# PA_Channel.net
KiCad netlist of a schematic drawn in Altium Designer
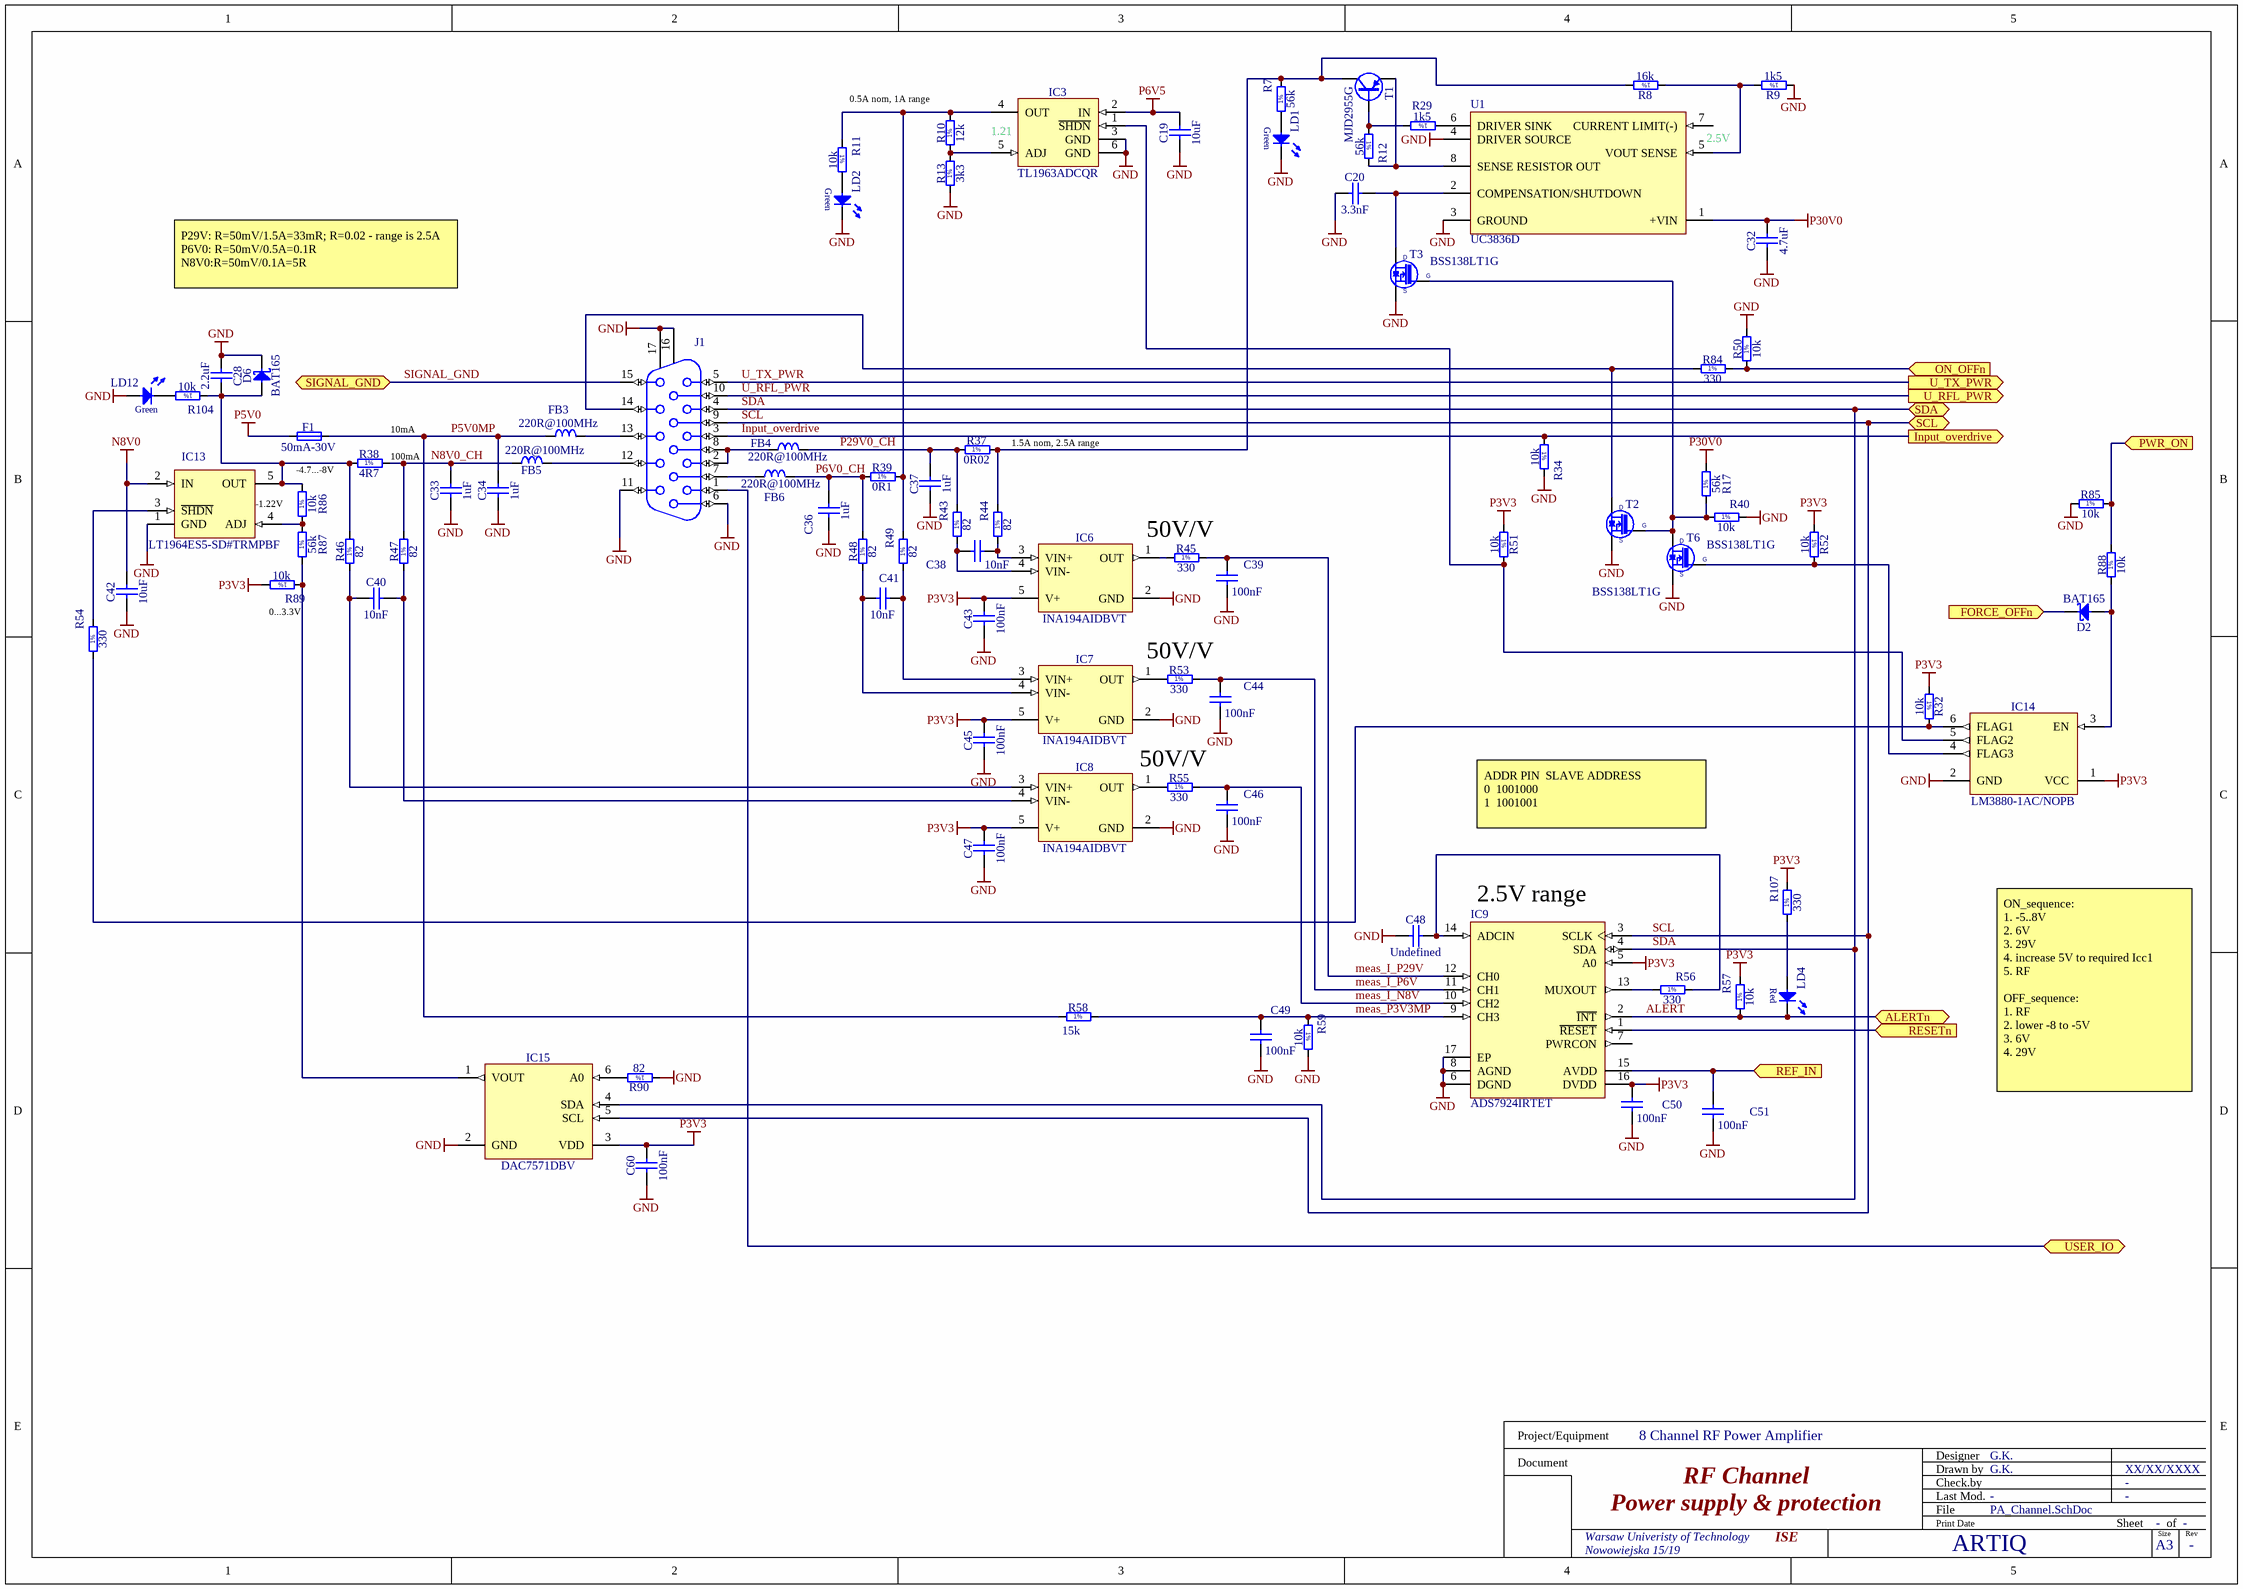
[diagram p0: PA_Channel.SchDoc]

(export (version "E")
  (design (tool "Eeschema 10.0.6"))
  (components
    (comp (ref "C19")
      (value "10uF")
      (footprint "CAPC3216X140N")
      (description "Non-polarised capacitor")
      (fields
        (field (name "PART NUMBER") "CC1206_10UF_16V_10%_X7R")
        (field (name "VOLTAGE") "16V")
        (field (name "AUTHOR") "CERN DEM JLC")
      )
      (libsource (lib "Capacitors") (part "Capacitor - non polarized"))
    )
    (comp (ref "C20")
      (value "3.3nF")
      (footprint "CAPC1005X55N")
      (description "Non-polarised capacitor")
      (fields
        (field (name "PART NUMBER") "CC0402_3.3NF_50V_10%_X7R")
        (field (name "VOLTAGE") "50V")
        (field (name "AUTHOR") "CERN DEM JLC")
      )
      (libsource (lib "Capacitors") (part "Capacitor - non polarized"))
    )
    (comp (ref "C28")
      (value "2.2uF")
      (footprint "CAPC1608X87N")
      (description "Non-polarised capacitor")
      (fields
        (field (name "PART NUMBER") "CC0603_2.2UF_16V_10%_X5R")
        (field (name "VOLTAGE") "16V")
        (field (name "AUTHOR") "CERN DEM JLC")
      )
      (libsource (lib "Capacitors") (part "Capacitor - non polarized"))
    )
    (comp (ref "C32")
      (value "4.7uF")
      (footprint "CAPC3216X180N")
      (description "Non-polarised capacitor")
      (fields
        (field (name "PART NUMBER") "CC1206_4.7UF_50V_+80%-20%_Y5V")
        (field (name "VOLTAGE") "50V")
        (field (name "AUTHOR") "CERN DEM JLC")
      )
      (libsource (lib "Capacitors") (part "Capacitor - non polarized"))
    )
    (comp (ref "C33")
      (value "1uF")
      (footprint "CAPC2012X110N")
      (description "Non-polarised capacitor")
      (fields
        (field (name "PART NUMBER") "CC0805_1UF_50V_10%_X7R")
        (field (name "VOLTAGE") "50V")
        (field (name "AUTHOR") "CERN DEM JLC")
      )
      (libsource (lib "Capacitors") (part "Capacitor - non polarized"))
    )
    (comp (ref "C34")
      (value "1uF")
      (footprint "CAPC2012X110N")
      (description "Non-polarised capacitor")
      (fields
        (field (name "PART NUMBER") "CC0805_1UF_50V_10%_X7R")
        (field (name "VOLTAGE") "50V")
        (field (name "AUTHOR") "CERN DEM JLC")
      )
      (libsource (lib "Capacitors") (part "Capacitor - non polarized"))
    )
    (comp (ref "C36")
      (value "1uF")
      (footprint "CAPC2012X110N")
      (description "Non-polarised capacitor")
      (fields
        (field (name "PART NUMBER") "CC0805_1UF_50V_10%_X7R")
        (field (name "VOLTAGE") "50V")
        (field (name "AUTHOR") "CERN DEM JLC")
      )
      (libsource (lib "Capacitors") (part "Capacitor - non polarized"))
    )
    (comp (ref "C37")
      (value "1uF")
      (footprint "CAPC2012X110N")
      (description "Non-polarised capacitor")
      (fields
        (field (name "PART NUMBER") "CC0805_1UF_50V_10%_X7R")
        (field (name "VOLTAGE") "50V")
        (field (name "AUTHOR") "CERN DEM JLC")
      )
      (libsource (lib "Capacitors") (part "Capacitor - non polarized"))
    )
    (comp (ref "C38")
      (value "10nF")
      (footprint "CAPC1608X87N")
      (description "Non-polarised capacitor")
      (fields
        (field (name "PART NUMBER") "CC0603_10NF_50V_5%_C0G")
        (field (name "VOLTAGE") "50V")
        (field (name "AUTHOR") "CERN DEM JLC")
      )
      (libsource (lib "Capacitors") (part "Capacitor - non polarized"))
    )
    (comp (ref "C39")
      (value "100nF")
      (footprint "CAPC1005X55N")
      (description "Non-polarised capacitor")
      (fields
        (field (name "PART NUMBER") "CC0402_100NF_16V_10%_X7R")
        (field (name "VOLTAGE") "16V")
        (field (name "AUTHOR") "CERN DEM JLC")
      )
      (libsource (lib "Capacitors") (part "Capacitor - non polarized"))
    )
    (comp (ref "C40")
      (value "10nF")
      (footprint "CAPC1608X87N")
      (description "Non-polarised capacitor")
      (fields
        (field (name "PART NUMBER") "CC0603_10NF_50V_5%_C0G")
        (field (name "VOLTAGE") "50V")
        (field (name "AUTHOR") "CERN DEM JLC")
      )
      (libsource (lib "Capacitors") (part "Capacitor - non polarized"))
    )
    (comp (ref "C41")
      (value "10nF")
      (footprint "CAPC1608X87N")
      (description "Non-polarised capacitor")
      (fields
        (field (name "PART NUMBER") "CC0603_10NF_50V_5%_C0G")
        (field (name "VOLTAGE") "50V")
        (field (name "AUTHOR") "CERN DEM JLC")
      )
      (libsource (lib "Capacitors") (part "Capacitor - non polarized"))
    )
    (comp (ref "C42")
      (value "10uF")
      (footprint "CAPC3216X140N")
      (description "Non-polarised capacitor")
      (fields
        (field (name "PART NUMBER") "CC1206_10UF_16V_10%_X7R")
        (field (name "VOLTAGE") "16V")
        (field (name "AUTHOR") "CERN DEM JLC")
      )
      (libsource (lib "Capacitors") (part "Capacitor - non polarized"))
    )
    (comp (ref "C43")
      (value "100nF")
      (footprint "CAPC1005X55N")
      (description "Non-polarised capacitor")
      (fields
        (field (name "PART NUMBER") "CC0402_100NF_16V_10%_X7R")
        (field (name "VOLTAGE") "16V")
        (field (name "AUTHOR") "CERN DEM JLC")
      )
      (libsource (lib "Capacitors") (part "Capacitor - non polarized"))
    )
    (comp (ref "C44")
      (value "100nF")
      (footprint "CAPC1005X55N")
      (description "Non-polarised capacitor")
      (fields
        (field (name "PART NUMBER") "CC0402_100NF_16V_10%_X7R")
        (field (name "VOLTAGE") "16V")
        (field (name "AUTHOR") "CERN DEM JLC")
      )
      (libsource (lib "Capacitors") (part "Capacitor - non polarized"))
    )
    (comp (ref "C45")
      (value "100nF")
      (footprint "CAPC1005X55N")
      (description "Non-polarised capacitor")
      (fields
        (field (name "PART NUMBER") "CC0402_100NF_16V_10%_X7R")
        (field (name "VOLTAGE") "16V")
        (field (name "AUTHOR") "CERN DEM JLC")
      )
      (libsource (lib "Capacitors") (part "Capacitor - non polarized"))
    )
    (comp (ref "C46")
      (value "100nF")
      (footprint "CAPC1005X55N")
      (description "Non-polarised capacitor")
      (fields
        (field (name "PART NUMBER") "CC0402_100NF_16V_10%_X7R")
        (field (name "VOLTAGE") "16V")
        (field (name "AUTHOR") "CERN DEM JLC")
      )
      (libsource (lib "Capacitors") (part "Capacitor - non polarized"))
    )
    (comp (ref "C47")
      (value "100nF")
      (footprint "CAPC1005X55N")
      (description "Non-polarised capacitor")
      (fields
        (field (name "PART NUMBER") "CC0402_100NF_16V_10%_X7R")
        (field (name "VOLTAGE") "16V")
        (field (name "AUTHOR") "CERN DEM JLC")
      )
      (libsource (lib "Capacitors") (part "Capacitor - non polarized"))
    )
    (comp (ref "C48")
      (value "Undefined")
      (footprint "CAPC1005X55N")
      (description "Non-polarised capacitor")
      (fields (field (name "PART NUMBER") "CC0402_NO-VALUE") (field (name "AUTHOR") "CERN DEM JLC"))
      (libsource (lib "Capacitors") (part "Capacitor - non polarized"))
    )
    (comp (ref "C49")
      (value "100nF")
      (footprint "CAPC1005X55N")
      (description "Non-polarised capacitor")
      (fields
        (field (name "PART NUMBER") "CC0402_100NF_16V_10%_X7R")
        (field (name "VOLTAGE") "16V")
        (field (name "AUTHOR") "CERN DEM JLC")
      )
      (libsource (lib "Capacitors") (part "Capacitor - non polarized"))
    )
    (comp (ref "C50")
      (value "100nF")
      (footprint "CAPC1005X55N")
      (description "Non-polarised capacitor")
      (fields
        (field (name "PART NUMBER") "CC0402_100NF_16V_10%_X7R")
        (field (name "VOLTAGE") "16V")
        (field (name "AUTHOR") "CERN DEM JLC")
      )
      (libsource (lib "Capacitors") (part "Capacitor - non polarized"))
    )
    (comp (ref "C51")
      (value "100nF")
      (footprint "CAPC1005X55N")
      (description "Non-polarised capacitor")
      (fields
        (field (name "PART NUMBER") "CC0402_100NF_16V_10%_X7R")
        (field (name "VOLTAGE") "16V")
        (field (name "AUTHOR") "CERN DEM JLC")
      )
      (libsource (lib "Capacitors") (part "Capacitor - non polarized"))
    )
    (comp (ref "C60")
      (value "100nF")
      (footprint "CAPC1005X55N")
      (description "Non-polarised capacitor")
      (fields
        (field (name "PART NUMBER") "CC0402_100NF_16V_10%_X7R")
        (field (name "VOLTAGE") "16V")
        (field (name "AUTHOR") "CERN DEM JLC")
      )
      (libsource (lib "Capacitors") (part "Capacitor - non polarized"))
    )
    (comp (ref "D2")
      (value "BAT165")
      (footprint "SOD2512X110N")
      (description "Schottky Diode")
      (fields
        (field (name "VOLTAGE") "40V")
        (field (name "POWER") "750mA")
        (field (name "AUTHOR") "CERN DEM JLC")
      )
      (libsource (lib "ICs And Semiconductors") (part "Diode Schottky"))
    )
    (comp (ref "D6")
      (value "BAT165")
      (footprint "SOD2512X110N")
      (description "Schottky Diode")
      (fields
        (field (name "VOLTAGE") "40V")
        (field (name "POWER") "750mA")
        (field (name "AUTHOR") "CERN DEM JLC")
      )
      (libsource (lib "ICs And Semiconductors") (part "Diode Schottky"))
    )
    (comp (ref "F1")
      (value "50mA-30V")
      (footprint "FUSRC3226X85N")
      (description "Fuse")
      (fields
        (field (name "PART NUMBER") "FUSR1210_TYCO-MICROSMD005F")
        (field (name "MANUFACTURER") "TYCO ELECTRONICS")
        (field (name "AUTHOR") "CERN DEM JLC")
      )
      (libsource (lib "Eletro-mechanical") (part "Fuse"))
    )
    (comp (ref "FB3")
      (value "220R@100MHz")
      (footprint "INDC2012X105N")
      (description "Inductor")
      (fields
        (field (name "PART NUMBER") "IND0805_MURATA_BLM21PG221SN1D")
        (field (name "POWER") "2A")
        (field (name "AUTHOR") "CERN DEM JLC")
      )
      (libsource (lib "Inductors & Transformers") (part "Inductor"))
    )
    (comp (ref "FB4")
      (value "220R@100MHz")
      (footprint "INDC2012X105N")
      (description "Inductor")
      (fields
        (field (name "PART NUMBER") "IND0805_MURATA_BLM21PG221SN1D")
        (field (name "POWER") "2A")
        (field (name "AUTHOR") "CERN DEM JLC")
      )
      (libsource (lib "Inductors & Transformers") (part "Inductor"))
    )
    (comp (ref "FB5")
      (value "220R@100MHz")
      (footprint "INDC2012X105N")
      (description "Inductor")
      (fields
        (field (name "PART NUMBER") "IND0805_MURATA_BLM21PG221SN1D")
        (field (name "POWER") "2A")
        (field (name "AUTHOR") "CERN DEM JLC")
      )
      (libsource (lib "Inductors & Transformers") (part "Inductor"))
    )
    (comp (ref "FB6")
      (value "220R@100MHz")
      (footprint "INDC2012X105N")
      (description "Inductor")
      (fields
        (field (name "PART NUMBER") "IND0805_MURATA_BLM21PG221SN1D")
        (field (name "POWER") "2A")
        (field (name "AUTHOR") "CERN DEM JLC")
      )
      (libsource (lib "Inductors & Transformers") (part "Inductor"))
    )
    (comp (ref "IC3")
      (value "TL1963ADCQR")
      (footprint "SOT127P700X180-6N")
      (description "1.2V to 20V, 1.5A, Fast Transient Response, Low Noise, LDO Adjustable Regulator")
      (fields (field (name "MANUFACTURER") "TEXAS INSTRUMENTS") (field (name "AUTHOR") "CERN DEM JLC"))
      (libsource (lib "ICs And Semiconductors") (part "TL1963ADCQR"))
    )
    (comp (ref "IC6")
      (value "INA194AIDBVT")
      (footprint "SOT95P280X145-5N")
      (description "Current Shunt Monitor -16V to +80V Common-Mode Range")
      (fields (field (name "MANUFACTURER") "TEXAS INSTRUMENTS") (field (name "AUTHOR") "CERN DEM JLC"))
      (libsource (lib "ICs And Semiconductors") (part "INA194"))
    )
    (comp (ref "IC7")
      (value "INA194AIDBVT")
      (footprint "SOT95P280X145-5N")
      (description "Current Shunt Monitor -16V to +80V Common-Mode Range")
      (fields (field (name "MANUFACTURER") "TEXAS INSTRUMENTS") (field (name "AUTHOR") "CERN DEM JLC"))
      (libsource (lib "ICs And Semiconductors") (part "INA194"))
    )
    (comp (ref "IC8")
      (value "INA194AIDBVT")
      (footprint "SOT95P280X145-5N")
      (description "Current Shunt Monitor -16V to +80V Common-Mode Range")
      (fields (field (name "MANUFACTURER") "TEXAS INSTRUMENTS") (field (name "AUTHOR") "CERN DEM JLC"))
      (libsource (lib "ICs And Semiconductors") (part "INA194"))
    )
    (comp (ref "IC9")
      (value "ADS7924IRTET")
      (footprint "TI-RTE16-1700X1700TP_V")
      (fields (field (name "MANUFACTURER") "Texas Instruments"))
      (libsource (lib "Altium Content Vault") (part "CMP-0003-02162-1"))
    )
    (comp (ref "IC13")
      (value "LT1964ES5-SD#TRMPBF")
      (footprint "SOT95P280X100-5N")
      (description "200mA, Low Noise, Low Dropout Negative Micropower Regulator")
      (fields (field (name "MANUFACTURER") "LINEAR TECHNOLOGY") (field (name "AUTHOR") "CERN DEM JLC"))
      (libsource (lib "ICs And Semiconductors") (part "LT1964-SD"))
    )
    (comp (ref "IC14")
      (value "LM3880-1AC/NOPB")
      (footprint "SOT95P280X145-6N")
      (description "Simple Power Sequencer")
      (fields (field (name "MANUFACTURER") "TEXAS INSTRUMENTS") (field (name "AUTHOR") "CERN DEM MR"))
      (libsource (lib "ICs And Semiconductors") (part "LM3880"))
    )
    (comp (ref "IC15")
      (value "DAC7571DBV")
      (footprint "SOT95P280X145-6N")
      (description "+2.7 V to +5.5 V, I2C Interface (Receive Only), Voltage Output, 12-Bit Digital-To-Analog Converter")
      (fields (field (name "MANUFACTURER") "TEXAS INSTRUMENTS") (field (name "AUTHOR") "CERN DEM MR"))
      (libsource (lib "ICs And Semiconductors") (part "DAC7571"))
    )
    (comp (ref "J1")
      (value "HD-Sub")
      (footprint "TYCO_1932144-1")
      (description "Connector High Density D-sub 15 Female")
      (fields
        (field (name "PART NUMBER") "TYCO_1932144-1")
        (field (name "MANUFACTURER") "TYCO ELECTRONICS")
        (field (name "AUTHOR") "GK")
      )
      (libsource (lib "LIBRARY_SCH") (part "CON_DB15_V_F_1932144-1"))
    )
    (comp (ref "LD1")
      (value "Green")
      (footprint "LED_KINGBRIGHT_KPH-1608CGCK")
      (description "LED Green 1C 2A")
      (fields
        (field (name "PART NUMBER") "LED_KINGBRIGHT_KPH-1608CGCK")
        (field (name "MANUFACTURER") "KINGBRIGHT")
        (field (name "AUTHOR") "CERN DEM JLC")
      )
      (libsource (lib "ICs And Semiconductors") (part "LED Green 1C 2A"))
    )
    (comp (ref "LD2")
      (value "Green")
      (footprint "LED_KINGBRIGHT_KPH-1608CGCK")
      (description "LED Green 1C 2A")
      (fields
        (field (name "PART NUMBER") "LED_KINGBRIGHT_KPH-1608CGCK")
        (field (name "MANUFACTURER") "KINGBRIGHT")
        (field (name "AUTHOR") "CERN DEM JLC")
      )
      (libsource (lib "ICs And Semiconductors") (part "LED Green 1C 2A"))
    )
    (comp (ref "LD4")
      (value "Hyper Red")
      (footprint "LED_KINGBRIGHT_KPH-1608SURCK")
      (description "LED Red 1C 2A")
      (fields
        (field (name "PART NUMBER") "LED_KINGBRIGHT_KPH-1608SURCK")
        (field (name "MANUFACTURER") "KINGBRIGHT")
        (field (name "AUTHOR") "CERN DEM JLC")
      )
      (libsource (lib "ICs And Semiconductors") (part "LED Red 1C 2A"))
    )
    (comp (ref "LD12")
      (value "Green")
      (footprint "LED_KINGBRIGHT_KPH-1608CGCK")
      (description "LED Green 1C 2A")
      (fields
        (field (name "PART NUMBER") "LED_KINGBRIGHT_KPH-1608CGCK")
        (field (name "MANUFACTURER") "KINGBRIGHT")
        (field (name "AUTHOR") "CERN DEM JLC")
      )
      (libsource (lib "ICs And Semiconductors") (part "LED Green 1C 2A"))
    )
    (comp (ref "R7")
      (value "56k")
      (footprint "RESC1608X55N")
      (description "Resistor - 1%")
      (fields
        (field (name "PART NUMBER") "R0603_56K_1%_0.1W_100PPM")
        (field (name "POWER") "0.1W")
        (field (name "AUTHOR") "CERN DEM JLC")
      )
      (libsource (lib "Resistors") (part "Resistor - 1%"))
    )
    (comp (ref "R8")
      (value "16k")
      (footprint "RESC1608X55N")
      (description "Resistor - 1%")
      (fields
        (field (name "PART NUMBER") "R0603_16K_1%_0.1W_100PPM")
        (field (name "POWER") "0.1W")
        (field (name "AUTHOR") "CERN DEM JLC")
      )
      (libsource (lib "Resistors") (part "Resistor - 1%"))
    )
    (comp (ref "R9")
      (value "1k5")
      (footprint "RESC1608X55N")
      (description "Resistor - 1%")
      (fields
        (field (name "PART NUMBER") "R0603_1K5_1%_0.1W_100PPM")
        (field (name "POWER") "0.1W")
        (field (name "AUTHOR") "CERN DEM JLC")
      )
      (libsource (lib "Resistors") (part "Resistor - 1%"))
    )
    (comp (ref "R10")
      (value "12k")
      (footprint "RESC1005X40N")
      (description "Resistor - 1%")
      (fields
        (field (name "PART NUMBER") "R0402_12K_1%_0.0625W_100PPM")
        (field (name "POWER") "0.0625W")
        (field (name "AUTHOR") "CERN DEM JLC")
      )
      (libsource (lib "Resistors") (part "Resistor - 1%"))
    )
    (comp (ref "R11")
      (value "10k")
      (footprint "RESC1005X40N")
      (description "Resistor - 1%")
      (fields
        (field (name "PART NUMBER") "R0402_10K_1%_0.0625W_100PPM")
        (field (name "POWER") "0.0625W")
        (field (name "AUTHOR") "CERN DEM JLC")
      )
      (libsource (lib "Resistors") (part "Resistor - 1%"))
    )
    (comp (ref "R12")
      (value "56k")
      (footprint "RESC1608X55N")
      (description "Resistor - 1%")
      (fields
        (field (name "PART NUMBER") "R0603_56K_1%_0.1W_100PPM")
        (field (name "POWER") "0.1W")
        (field (name "AUTHOR") "CERN DEM JLC")
      )
      (libsource (lib "Resistors") (part "Resistor - 1%"))
    )
    (comp (ref "R13")
      (value "3k3")
      (footprint "RESC1005X40N")
      (description "Resistor - 1%")
      (fields
        (field (name "PART NUMBER") "R0402_3K3_1%_0.0625W_100PPM")
        (field (name "POWER") "0.0625W")
        (field (name "AUTHOR") "CERN DEM JLC")
      )
      (libsource (lib "Resistors") (part "Resistor - 1%"))
    )
    (comp (ref "R17")
      (value "56k")
      (footprint "RESC1608X55N")
      (description "Resistor - 1%")
      (fields
        (field (name "PART NUMBER") "R0603_56K_1%_0.1W_100PPM")
        (field (name "POWER") "0.1W")
        (field (name "AUTHOR") "CERN DEM JLC")
      )
      (libsource (lib "Resistors") (part "Resistor - 1%"))
    )
    (comp (ref "R29")
      (value "1k5")
      (footprint "RESC1608X55N")
      (description "Resistor - 1%")
      (fields
        (field (name "PART NUMBER") "R0603_1K5_1%_0.1W_100PPM")
        (field (name "POWER") "0.1W")
        (field (name "AUTHOR") "CERN DEM JLC")
      )
      (libsource (lib "Resistors") (part "Resistor - 1%"))
    )
    (comp (ref "R32")
      (value "10k")
      (footprint "RESC1005X40N")
      (description "Resistor - 1%")
      (fields
        (field (name "PART NUMBER") "R0402_10K_1%_0.0625W_100PPM")
        (field (name "POWER") "0.0625W")
        (field (name "AUTHOR") "CERN DEM JLC")
      )
      (libsource (lib "Resistors") (part "Resistor - 1%"))
    )
    (comp (ref "R34")
      (value "10k")
      (footprint "RESC1005X40N")
      (description "Resistor - 1%")
      (fields
        (field (name "PART NUMBER") "R0402_10K_1%_0.0625W_100PPM")
        (field (name "POWER") "0.0625W")
        (field (name "AUTHOR") "CERN DEM JLC")
      )
      (libsource (lib "Resistors") (part "Resistor - 1%"))
    )
    (comp (ref "R37")
      (value "0R02")
      (footprint "RESC3216X80N")
      (description "Resistor - 1%")
      (fields
        (field (name "PART NUMBER") "R1206_0R02_1%_1W_150PPM")
        (field (name "POWER") "1W")
        (field (name "AUTHOR") "CERN DEM JLC")
      )
      (libsource (lib "Resistors") (part "Resistor - 1%"))
    )
    (comp (ref "R38")
      (value "4R7")
      (footprint "RESC3216X65N")
      (description "Resistor - 1%")
      (fields
        (field (name "PART NUMBER") "R1206_4R7_1%_0.25W_200PPM")
        (field (name "POWER") "0.25W")
        (field (name "AUTHOR") "CERN DEM JLC")
      )
      (libsource (lib "Resistors") (part "Resistor - 1%"))
    )
    (comp (ref "R39")
      (value "0R1")
      (footprint "RESC3216X65N")
      (description "Resistor - 1%")
      (fields
        (field (name "PART NUMBER") "R1206_0R1_1%_0.25W_100PPM_YAGEO_PT")
        (field (name "POWER") "0.25W")
        (field (name "AUTHOR") "CERN DEM JMW")
      )
      (libsource (lib "Resistors") (part "Resistor - 1%"))
    )
    (comp (ref "R40")
      (value "10k")
      (footprint "RESC1005X40N")
      (description "Resistor - 1%")
      (fields
        (field (name "PART NUMBER") "R0402_10K_1%_0.0625W_100PPM")
        (field (name "POWER") "0.0625W")
        (field (name "AUTHOR") "CERN DEM JLC")
      )
      (libsource (lib "Resistors") (part "Resistor - 1%"))
    )
    (comp (ref "R43")
      (value "82")
      (footprint "RESC1005X40N")
      (description "Resistor - 1%")
      (fields
        (field (name "PART NUMBER") "R0402_82R_1%_0.0625W_100PPM")
        (field (name "POWER") "0.0625W")
        (field (name "AUTHOR") "CERN DEM JLC")
      )
      (libsource (lib "Resistors") (part "Resistor - 1%"))
    )
    (comp (ref "R44")
      (value "82")
      (footprint "RESC1005X40N")
      (description "Resistor - 1%")
      (fields
        (field (name "PART NUMBER") "R0402_82R_1%_0.0625W_100PPM")
        (field (name "POWER") "0.0625W")
        (field (name "AUTHOR") "CERN DEM JLC")
      )
      (libsource (lib "Resistors") (part "Resistor - 1%"))
    )
    (comp (ref "R45")
      (value "330")
      (footprint "RESC1608X55N")
      (description "Resistor - 1%")
      (fields
        (field (name "PART NUMBER") "R0603_330R_1%_0.1W_100PPM")
        (field (name "POWER") "0.1W")
        (field (name "AUTHOR") "CERN DEM JLC")
      )
      (libsource (lib "Resistors") (part "Resistor - 1%"))
    )
    (comp (ref "R46")
      (value "82")
      (footprint "RESC1005X40N")
      (description "Resistor - 1%")
      (fields
        (field (name "PART NUMBER") "R0402_82R_1%_0.0625W_100PPM")
        (field (name "POWER") "0.0625W")
        (field (name "AUTHOR") "CERN DEM JLC")
      )
      (libsource (lib "Resistors") (part "Resistor - 1%"))
    )
    (comp (ref "R47")
      (value "82")
      (footprint "RESC1005X40N")
      (description "Resistor - 1%")
      (fields
        (field (name "PART NUMBER") "R0402_82R_1%_0.0625W_100PPM")
        (field (name "POWER") "0.0625W")
        (field (name "AUTHOR") "CERN DEM JLC")
      )
      (libsource (lib "Resistors") (part "Resistor - 1%"))
    )
    (comp (ref "R48")
      (value "82")
      (footprint "RESC1005X40N")
      (description "Resistor - 1%")
      (fields
        (field (name "PART NUMBER") "R0402_82R_1%_0.0625W_100PPM")
        (field (name "POWER") "0.0625W")
        (field (name "AUTHOR") "CERN DEM JLC")
      )
      (libsource (lib "Resistors") (part "Resistor - 1%"))
    )
    (comp (ref "R49")
      (value "82")
      (footprint "RESC1005X40N")
      (description "Resistor - 1%")
      (fields
        (field (name "PART NUMBER") "R0402_82R_1%_0.0625W_100PPM")
        (field (name "POWER") "0.0625W")
        (field (name "AUTHOR") "CERN DEM JLC")
      )
      (libsource (lib "Resistors") (part "Resistor - 1%"))
    )
    (comp (ref "R50")
      (value "10k")
      (footprint "RESC1005X40N")
      (description "Resistor - 1%")
      (fields
        (field (name "PART NUMBER") "R0402_10K_1%_0.0625W_100PPM")
        (field (name "POWER") "0.0625W")
        (field (name "AUTHOR") "CERN DEM JLC")
      )
      (libsource (lib "Resistors") (part "Resistor - 1%"))
    )
    (comp (ref "R51")
      (value "10k")
      (footprint "RESC1005X40N")
      (description "Resistor - 1%")
      (fields
        (field (name "PART NUMBER") "R0402_10K_1%_0.0625W_100PPM")
        (field (name "POWER") "0.0625W")
        (field (name "AUTHOR") "CERN DEM JLC")
      )
      (libsource (lib "Resistors") (part "Resistor - 1%"))
    )
    (comp (ref "R52")
      (value "10k")
      (footprint "RESC1005X40N")
      (description "Resistor - 1%")
      (fields
        (field (name "PART NUMBER") "R0402_10K_1%_0.0625W_100PPM")
        (field (name "POWER") "0.0625W")
        (field (name "AUTHOR") "CERN DEM JLC")
      )
      (libsource (lib "Resistors") (part "Resistor - 1%"))
    )
    (comp (ref "R53")
      (value "330")
      (footprint "RESC1608X55N")
      (description "Resistor - 1%")
      (fields
        (field (name "PART NUMBER") "R0603_330R_1%_0.1W_100PPM")
        (field (name "POWER") "0.1W")
        (field (name "AUTHOR") "CERN DEM JLC")
      )
      (libsource (lib "Resistors") (part "Resistor - 1%"))
    )
    (comp (ref "R54")
      (value "330")
      (footprint "RESC1608X55N")
      (description "Resistor - 1%")
      (fields
        (field (name "PART NUMBER") "R0603_330R_1%_0.1W_100PPM")
        (field (name "POWER") "0.1W")
        (field (name "AUTHOR") "CERN DEM JLC")
      )
      (libsource (lib "Resistors") (part "Resistor - 1%"))
    )
    (comp (ref "R55")
      (value "330")
      (footprint "RESC1608X55N")
      (description "Resistor - 1%")
      (fields
        (field (name "PART NUMBER") "R0603_330R_1%_0.1W_100PPM")
        (field (name "POWER") "0.1W")
        (field (name "AUTHOR") "CERN DEM JLC")
      )
      (libsource (lib "Resistors") (part "Resistor - 1%"))
    )
    (comp (ref "R56")
      (value "330")
      (footprint "RESC1608X55N")
      (description "Resistor - 1%")
      (fields
        (field (name "PART NUMBER") "R0603_330R_1%_0.1W_100PPM")
        (field (name "POWER") "0.1W")
        (field (name "AUTHOR") "CERN DEM JLC")
      )
      (libsource (lib "Resistors") (part "Resistor - 1%"))
    )
    (comp (ref "R57")
      (value "10k")
      (footprint "RESC1005X40N")
      (description "Resistor - 1%")
      (fields
        (field (name "PART NUMBER") "R0402_10K_1%_0.0625W_100PPM")
        (field (name "POWER") "0.0625W")
        (field (name "AUTHOR") "CERN DEM JLC")
      )
      (libsource (lib "Resistors") (part "Resistor - 1%"))
    )
    (comp (ref "R58")
      (value "15k")
      (footprint "RESC1005X40N")
      (description "Resistor - 1%")
      (fields
        (field (name "PART NUMBER") "R0402_15K_1%_0.0625W_100PPM")
        (field (name "POWER") "0.0625W")
        (field (name "AUTHOR") "CERN DEM JMW")
      )
      (libsource (lib "Resistors") (part "Resistor - 1%"))
    )
    (comp (ref "R59")
      (value "10k")
      (footprint "RESC1005X40N")
      (description "Resistor - 1%")
      (fields
        (field (name "PART NUMBER") "R0402_10K_1%_0.0625W_100PPM")
        (field (name "POWER") "0.0625W")
        (field (name "AUTHOR") "CERN DEM JLC")
      )
      (libsource (lib "Resistors") (part "Resistor - 1%"))
    )
    (comp (ref "R84")
      (value "330")
      (footprint "RESC1608X55N")
      (description "Resistor - 1%")
      (fields
        (field (name "PART NUMBER") "R0603_330R_1%_0.1W_100PPM")
        (field (name "POWER") "0.1W")
        (field (name "AUTHOR") "CERN DEM JLC")
      )
      (libsource (lib "Resistors") (part "Resistor - 1%"))
    )
    (comp (ref "R85")
      (value "10k")
      (footprint "RESC1005X40N")
      (description "Resistor - 1%")
      (fields
        (field (name "PART NUMBER") "R0402_10K_1%_0.0625W_100PPM")
        (field (name "POWER") "0.0625W")
        (field (name "AUTHOR") "CERN DEM JLC")
      )
      (libsource (lib "Resistors") (part "Resistor - 1%"))
    )
    (comp (ref "R86")
      (value "10k")
      (footprint "RESC1005X40N")
      (description "Resistor - 1%")
      (fields
        (field (name "PART NUMBER") "R0402_10K_1%_0.0625W_100PPM")
        (field (name "POWER") "0.0625W")
        (field (name "AUTHOR") "CERN DEM JLC")
      )
      (libsource (lib "Resistors") (part "Resistor - 1%"))
    )
    (comp (ref "R87")
      (value "56k")
      (footprint "RESC1608X55N")
      (description "Resistor - 1%")
      (fields
        (field (name "PART NUMBER") "R0603_56K_1%_0.1W_100PPM")
        (field (name "POWER") "0.1W")
        (field (name "AUTHOR") "CERN DEM JLC")
      )
      (libsource (lib "Resistors") (part "Resistor - 1%"))
    )
    (comp (ref "R88")
      (value "10k")
      (footprint "RESC1005X40N")
      (description "Resistor - 1%")
      (fields
        (field (name "PART NUMBER") "R0402_10K_1%_0.0625W_100PPM")
        (field (name "POWER") "0.0625W")
        (field (name "AUTHOR") "CERN DEM JLC")
      )
      (libsource (lib "Resistors") (part "Resistor - 1%"))
    )
    (comp (ref "R89")
      (value "10k")
      (footprint "RESC1005X40N")
      (description "Resistor - 1%")
      (fields
        (field (name "PART NUMBER") "R0402_10K_1%_0.0625W_100PPM")
        (field (name "POWER") "0.0625W")
        (field (name "AUTHOR") "CERN DEM JLC")
      )
      (libsource (lib "Resistors") (part "Resistor - 1%"))
    )
    (comp (ref "R90")
      (value "82")
      (footprint "RESC1005X40N")
      (description "Resistor - 1%")
      (fields
        (field (name "PART NUMBER") "R0402_82R_1%_0.0625W_100PPM")
        (field (name "POWER") "0.0625W")
        (field (name "AUTHOR") "CERN DEM JLC")
      )
      (libsource (lib "Resistors") (part "Resistor - 1%"))
    )
    (comp (ref "R104")
      (value "10k")
      (footprint "RESC1005X40N")
      (description "Resistor - 1%")
      (fields
        (field (name "PART NUMBER") "R0402_10K_1%_0.0625W_100PPM")
        (field (name "POWER") "0.0625W")
        (field (name "AUTHOR") "CERN DEM JLC")
      )
      (libsource (lib "Resistors") (part "Resistor - 1%"))
    )
    (comp (ref "R107")
      (value "330")
      (footprint "RESC1608X55N")
      (description "Resistor - 1%")
      (fields
        (field (name "PART NUMBER") "R0603_330R_1%_0.1W_100PPM")
        (field (name "POWER") "0.1W")
        (field (name "AUTHOR") "CERN DEM JLC")
      )
      (libsource (lib "Resistors") (part "Resistor - 1%"))
    )
    (comp (ref "T1")
      (value "MJD2955G")
      (footprint "TO228P991X239-3N-R552X520")
      (description "PNP Transistor")
      (fields (field (name "MANUFACTURER") "ON SEMICONDUCTOR") (field (name "AUTHOR") "CERN DEM JLC"))
      (libsource (lib "ICs And Semiconductors") (part "PNP B1 E2 C3"))
    )
    (comp (ref "T2")
      (value "BSS138LT1G")
      (footprint "SOT95P240X110-3N")
      (description "N-CHANNEL MOSFET WITH DIODE")
      (fields (field (name "MANUFACTURER") "ON SEMICONDUCTOR") (field (name "AUTHOR") "CERN DEM JLC"))
      (libsource (lib "ICs And Semiconductors") (part "N-MOSFET-D 1G 2S 3D"))
    )
    (comp (ref "T3")
      (value "BSS138LT1G")
      (footprint "SOT95P240X110-3N")
      (description "N-CHANNEL MOSFET WITH DIODE")
      (fields (field (name "MANUFACTURER") "ON SEMICONDUCTOR") (field (name "AUTHOR") "CERN DEM JLC"))
      (libsource (lib "ICs And Semiconductors") (part "N-MOSFET-D 1G 2S 3D"))
    )
    (comp (ref "T6")
      (value "BSS138LT1G")
      (footprint "SOT95P240X110-3N")
      (description "N-CHANNEL MOSFET WITH DIODE")
      (fields (field (name "MANUFACTURER") "ON SEMICONDUCTOR") (field (name "AUTHOR") "CERN DEM JLC"))
      (libsource (lib "ICs And Semiconductors") (part "N-MOSFET-D 1G 2S 3D"))
    )
    (comp (ref "U1")
      (value "UC3836D")
      (footprint "D0008A_M")
      (fields (field (name "MANUFACTURER") "Texas Instruments"))
      (libsource (lib "Altium Content Vault") (part "CMP-0322-00047-2"))
    )
  )
  (nets
    (net (code "1") (name "/ALERT") (class "Default")
      (node (ref "IC9") (pin "2") (pinfunction "~{INT}_2") (pintype "output"))
      (node (ref "LD4") (pin "1") (pinfunction "C_1") (pintype "passive"))
      (node (ref "R57") (pin "1") (pinfunction "1_1") (pintype "passive"))
    )
    (net (code "2") (name "/FORCE_OFFn") (class "Default")
      (node (ref "D2") (pin "1") (pinfunction "C_1") (pintype "passive"))
    )
    (net (code "3") (name "/Input_overdrive") (class "Default")
      (node (ref "J1") (pin "3") (pinfunction "3_3") (pintype "bidirectional"))
      (node (ref "R34") (pin "1") (pinfunction "1_1") (pintype "passive"))
    )
    (net (code "4") (name "/N8V0_CH") (class "Default")
      (node (ref "C33") (pin "2") (pinfunction "2_2") (pintype "passive"))
      (node (ref "FB5") (pin "1") (pinfunction "1_1") (pintype "passive"))
      (node (ref "R38") (pin "2") (pinfunction "2_2") (pintype "passive"))
      (node (ref "R47") (pin "2") (pinfunction "2_2") (pintype "passive"))
    )
    (net (code "5") (name "/ON_OFFn") (class "Default")
      (node (ref "R50") (pin "1") (pinfunction "1_1") (pintype "passive"))
      (node (ref "R84") (pin "2") (pinfunction "2_2") (pintype "passive"))
    )
    (net (code "6") (name "/P5V0MP") (class "Default")
      (node (ref "C34") (pin "2") (pinfunction "2_2") (pintype "passive"))
      (node (ref "F1") (pin "2") (pinfunction "2_2") (pintype "passive"))
      (node (ref "FB3") (pin "1") (pinfunction "1_1") (pintype "passive"))
      (node (ref "R58") (pin "1") (pinfunction "1_1") (pintype "passive"))
    )
    (net (code "7") (name "/P6V0_CH") (class "Default")
      (node (ref "C36") (pin "2") (pinfunction "2_2") (pintype "passive"))
      (node (ref "FB6") (pin "2") (pinfunction "2_2") (pintype "passive"))
      (node (ref "R39") (pin "1") (pinfunction "1_1") (pintype "passive"))
      (node (ref "R48") (pin "2") (pinfunction "2_2") (pintype "passive"))
    )
    (net (code "8") (name "/P29V0_CH") (class "Default")
      (node (ref "C37") (pin "2") (pinfunction "2_2") (pintype "passive"))
      (node (ref "FB4") (pin "2") (pinfunction "2_2") (pintype "passive"))
      (node (ref "R37") (pin "1") (pinfunction "1_1") (pintype "passive"))
      (node (ref "R43") (pin "2") (pinfunction "2_2") (pintype "passive"))
    )
    (net (code "9") (name "/PWR_ON") (class "Default")
      (node (ref "R85") (pin "2") (pinfunction "2_2") (pintype "passive"))
      (node (ref "R88") (pin "2") (pinfunction "2_2") (pintype "passive"))
    )
    (net (code "10") (name "/REF_IN") (class "Default")
      (node (ref "C51") (pin "1") (pinfunction "1_1") (pintype "passive"))
      (node (ref "IC9") (pin "15") (pinfunction "AVDD_15") (pintype "power_in"))
    )
    (net (code "11") (name "/RESETn") (class "Default")
      (node (ref "IC9") (pin "1") (pinfunction "~{RESET}_1") (pintype "input"))
    )
    (net (code "12") (name "/SCL") (class "Default")
      (node (ref "IC15") (pin "5") (pinfunction "SCL_5") (pintype "input"))
      (node (ref "IC9") (pin "3") (pinfunction "SCLK_3") (pintype "input"))
      (node (ref "J1") (pin "9") (pinfunction "9_9") (pintype "bidirectional"))
    )
    (net (code "13") (name "/SDA") (class "Default")
      (node (ref "IC15") (pin "4") (pinfunction "SDA_4") (pintype "input"))
      (node (ref "IC9") (pin "4") (pinfunction "SDA_4") (pintype "bidirectional"))
      (node (ref "J1") (pin "4") (pinfunction "4_4") (pintype "bidirectional"))
    )
    (net (code "14") (name "/SIGNAL_GND") (class "Default")
      (node (ref "J1") (pin "15") (pinfunction "15_15") (pintype "bidirectional"))
    )
    (net (code "15") (name "/USER_IO") (class "Default")
      (node (ref "J1") (pin "1") (pinfunction "1_1") (pintype "bidirectional"))
    )
    (net (code "16") (name "/U_RFL_PWR") (class "Default")
      (node (ref "J1") (pin "10") (pinfunction "10_10") (pintype "bidirectional"))
    )
    (net (code "17") (name "/U_TX_PWR") (class "Default")
      (node (ref "J1") (pin "5") (pinfunction "5_5") (pintype "bidirectional"))
    )
    (net (code "18") (name "/meas_I_N8V") (class "Default")
      (node (ref "C46") (pin "1") (pinfunction "1_1") (pintype "passive"))
      (node (ref "IC9") (pin "10") (pinfunction "CH2_10") (pintype "input"))
      (node (ref "R55") (pin "2") (pinfunction "2_2") (pintype "passive"))
    )
    (net (code "19") (name "/meas_I_P6V") (class "Default")
      (node (ref "C44") (pin "1") (pinfunction "1_1") (pintype "passive"))
      (node (ref "IC9") (pin "11") (pinfunction "CH1_11") (pintype "input"))
      (node (ref "R53") (pin "2") (pinfunction "2_2") (pintype "passive"))
    )
    (net (code "20") (name "/meas_I_P29V") (class "Default")
      (node (ref "C39") (pin "1") (pinfunction "1_1") (pintype "passive"))
      (node (ref "IC9") (pin "12") (pinfunction "CH0_12") (pintype "input"))
      (node (ref "R45") (pin "2") (pinfunction "2_2") (pintype "passive"))
    )
    (net (code "21") (name "/meas_P3V3MP") (class "Default")
      (node (ref "C49") (pin "1") (pinfunction "1_1") (pintype "passive"))
      (node (ref "IC9") (pin "9") (pinfunction "CH3_9") (pintype "input"))
      (node (ref "R58") (pin "2") (pinfunction "2_2") (pintype "passive"))
      (node (ref "R59") (pin "1") (pinfunction "1_1") (pintype "passive"))
    )
    (net (code "22") (name "GND") (class "Default")
      (node (ref "C19") (pin "1") (pinfunction "1_1") (pintype "passive"))
      (node (ref "C20") (pin "1") (pinfunction "1_1") (pintype "passive"))
      (node (ref "C28") (pin "1") (pinfunction "1_1") (pintype "passive"))
      (node (ref "C32") (pin "1") (pinfunction "1_1") (pintype "passive"))
      (node (ref "C33") (pin "1") (pinfunction "1_1") (pintype "passive"))
      (node (ref "C34") (pin "1") (pinfunction "1_1") (pintype "passive"))
      (node (ref "C36") (pin "1") (pinfunction "1_1") (pintype "passive"))
      (node (ref "C37") (pin "1") (pinfunction "1_1") (pintype "passive"))
      (node (ref "C39") (pin "2") (pinfunction "2_2") (pintype "passive"))
      (node (ref "C42") (pin "1") (pinfunction "1_1") (pintype "passive"))
      (node (ref "C43") (pin "1") (pinfunction "1_1") (pintype "passive"))
      (node (ref "C44") (pin "2") (pinfunction "2_2") (pintype "passive"))
      (node (ref "C45") (pin "1") (pinfunction "1_1") (pintype "passive"))
      (node (ref "C46") (pin "2") (pinfunction "2_2") (pintype "passive"))
      (node (ref "C47") (pin "1") (pinfunction "1_1") (pintype "passive"))
      (node (ref "C48") (pin "1") (pinfunction "1_1") (pintype "passive"))
      (node (ref "C49") (pin "2") (pinfunction "2_2") (pintype "passive"))
      (node (ref "C50") (pin "2") (pinfunction "2_2") (pintype "passive"))
      (node (ref "C51") (pin "2") (pinfunction "2_2") (pintype "passive"))
      (node (ref "C60") (pin "1") (pinfunction "1_1") (pintype "passive"))
      (node (ref "D6") (pin "1") (pinfunction "C_1") (pintype "passive"))
      (node (ref "IC13") (pin "1") (pinfunction "GND_1") (pintype "power_in"))
      (node (ref "IC14") (pin "2") (pinfunction "GND_2") (pintype "power_in"))
      (node (ref "IC15") (pin "2") (pinfunction "GND_2") (pintype "power_in"))
      (node (ref "IC3") (pin "3") (pinfunction "GND_3") (pintype "power_in"))
      (node (ref "IC3") (pin "6") (pinfunction "GND_6") (pintype "power_in"))
      (node (ref "IC6") (pin "2") (pinfunction "GND_2") (pintype "power_in"))
      (node (ref "IC7") (pin "2") (pinfunction "GND_2") (pintype "power_in"))
      (node (ref "IC8") (pin "2") (pinfunction "GND_2") (pintype "power_in"))
      (node (ref "IC9") (pin "17") (pinfunction "EP_17") (pintype "power_in"))
      (node (ref "IC9") (pin "6") (pinfunction "DGND_6") (pintype "power_in"))
      (node (ref "IC9") (pin "8") (pinfunction "AGND_8") (pintype "power_in"))
      (node (ref "J1") (pin "11") (pinfunction "11_11") (pintype "bidirectional"))
      (node (ref "J1") (pin "16") (pinfunction "16_16") (pintype "passive"))
      (node (ref "J1") (pin "17") (pinfunction "17_17") (pintype "passive"))
      (node (ref "J1") (pin "6") (pinfunction "6_6") (pintype "bidirectional"))
      (node (ref "LD1") (pin "1") (pinfunction "C_1") (pintype "passive"))
      (node (ref "LD12") (pin "2") (pinfunction "A_2") (pintype "passive"))
      (node (ref "LD2") (pin "1") (pinfunction "C_1") (pintype "passive"))
      (node (ref "R13") (pin "1") (pinfunction "1_1") (pintype "passive"))
      (node (ref "R34") (pin "2") (pinfunction "2_2") (pintype "passive"))
      (node (ref "R40") (pin "2") (pinfunction "2_2") (pintype "passive"))
      (node (ref "R50") (pin "2") (pinfunction "2_2") (pintype "passive"))
      (node (ref "R59") (pin "2") (pinfunction "2_2") (pintype "passive"))
      (node (ref "R85") (pin "1") (pinfunction "1_1") (pintype "passive"))
      (node (ref "R9") (pin "1") (pinfunction "1_1") (pintype "passive"))
      (node (ref "R90") (pin "1") (pinfunction "1_1") (pintype "passive"))
      (node (ref "T2") (pin "2") (pinfunction "S_2") (pintype "passive"))
      (node (ref "T3") (pin "2") (pinfunction "S_2") (pintype "passive"))
      (node (ref "T6") (pin "2") (pinfunction "S_2") (pintype "passive"))
      (node (ref "U1") (pin "3") (pinfunction "GROUND_3") (pintype "power_in"))
      (node (ref "U1") (pin "4") (pinfunction "DRIVER_SOURCE_4") (pintype "passive"))
    )
    (net (code "23") (name "N8V0") (class "Default")
      (node (ref "C42") (pin "2") (pinfunction "2_2") (pintype "passive"))
      (node (ref "IC13") (pin "2") (pinfunction "IN_2") (pintype "input"))
    )
    (net (code "24") (name "Net-(D2-A)") (class "Default")
      (node (ref "D2") (pin "2") (pinfunction "A_2") (pintype "passive"))
      (node (ref "IC14") (pin "3") (pinfunction "EN_3") (pintype "input"))
      (node (ref "R88") (pin "1") (pinfunction "1_1") (pintype "passive"))
    )
    (net (code "25") (name "Net-(D6-A)") (class "Default")
      (node (ref "C28") (pin "2") (pinfunction "2_2") (pintype "passive"))
      (node (ref "D6") (pin "2") (pinfunction "A_2") (pintype "passive"))
      (node (ref "IC13") (pin "5") (pinfunction "OUT_5") (pintype "power_in"))
      (node (ref "R104") (pin "1") (pinfunction "1_1") (pintype "passive"))
      (node (ref "R38") (pin "1") (pinfunction "1_1") (pintype "passive"))
      (node (ref "R46") (pin "2") (pinfunction "2_2") (pintype "passive"))
      (node (ref "R86") (pin "2") (pinfunction "2_2") (pintype "passive"))
    )
    (net (code "26") (name "Net-(FB3-Pad2)") (class "Default")
      (node (ref "FB3") (pin "2") (pinfunction "2_2") (pintype "passive"))
      (node (ref "J1") (pin "13") (pinfunction "13_13") (pintype "bidirectional"))
    )
    (net (code "27") (name "Net-(FB4-Pad1)") (class "Default")
      (node (ref "FB4") (pin "1") (pinfunction "1_1") (pintype "passive"))
      (node (ref "J1") (pin "2") (pinfunction "2_2") (pintype "bidirectional"))
      (node (ref "J1") (pin "8") (pinfunction "8_8") (pintype "bidirectional"))
    )
    (net (code "28") (name "Net-(FB5-Pad2)") (class "Default")
      (node (ref "FB5") (pin "2") (pinfunction "2_2") (pintype "passive"))
      (node (ref "J1") (pin "12") (pinfunction "12_12") (pintype "bidirectional"))
    )
    (net (code "29") (name "Net-(FB6-Pad1)") (class "Default")
      (node (ref "FB6") (pin "1") (pinfunction "1_1") (pintype "passive"))
      (node (ref "J1") (pin "7") (pinfunction "7_7") (pintype "bidirectional"))
    )
    (net (code "30") (name "Net-(IC3-ADJ)") (class "Default")
      (node (ref "IC3") (pin "5") (pinfunction "ADJ_5") (pintype "input"))
      (node (ref "R10") (pin "1") (pinfunction "1_1") (pintype "passive"))
      (node (ref "R13") (pin "2") (pinfunction "2_2") (pintype "passive"))
    )
    (net (code "31") (name "Net-(IC3-OUT)") (class "Default")
      (node (ref "IC3") (pin "4") (pinfunction "OUT_4") (pintype "power_in"))
      (node (ref "R10") (pin "2") (pinfunction "2_2") (pintype "passive"))
      (node (ref "R11") (pin "1") (pinfunction "1_1") (pintype "passive"))
      (node (ref "R39") (pin "2") (pinfunction "2_2") (pintype "passive"))
      (node (ref "R49") (pin "2") (pinfunction "2_2") (pintype "passive"))
    )
    (net (code "32") (name "Net-(IC6-OUT)") (class "Default")
      (node (ref "IC6") (pin "1") (pinfunction "OUT_1") (pintype "output"))
      (node (ref "R45") (pin "1") (pinfunction "1_1") (pintype "passive"))
    )
    (net (code "33") (name "Net-(IC6-VIN+)") (class "Default")
      (node (ref "C38") (pin "2") (pinfunction "2_2") (pintype "passive"))
      (node (ref "IC6") (pin "3") (pinfunction "VIN+_3") (pintype "input"))
      (node (ref "R44") (pin "1") (pinfunction "1_1") (pintype "passive"))
    )
    (net (code "34") (name "Net-(IC6-VIN-)") (class "Default")
      (node (ref "C38") (pin "1") (pinfunction "1_1") (pintype "passive"))
      (node (ref "IC6") (pin "4") (pinfunction "VIN-_4") (pintype "input"))
      (node (ref "R43") (pin "1") (pinfunction "1_1") (pintype "passive"))
    )
    (net (code "35") (name "Net-(IC7-OUT)") (class "Default")
      (node (ref "IC7") (pin "1") (pinfunction "OUT_1") (pintype "output"))
      (node (ref "R53") (pin "1") (pinfunction "1_1") (pintype "passive"))
    )
    (net (code "36") (name "Net-(IC7-VIN+)") (class "Default")
      (node (ref "C41") (pin "2") (pinfunction "2_2") (pintype "passive"))
      (node (ref "IC7") (pin "3") (pinfunction "VIN+_3") (pintype "input"))
      (node (ref "R49") (pin "1") (pinfunction "1_1") (pintype "passive"))
    )
    (net (code "37") (name "Net-(IC7-VIN-)") (class "Default")
      (node (ref "C41") (pin "1") (pinfunction "1_1") (pintype "passive"))
      (node (ref "IC7") (pin "4") (pinfunction "VIN-_4") (pintype "input"))
      (node (ref "R48") (pin "1") (pinfunction "1_1") (pintype "passive"))
    )
    (net (code "38") (name "Net-(IC8-OUT)") (class "Default")
      (node (ref "IC8") (pin "1") (pinfunction "OUT_1") (pintype "output"))
      (node (ref "R55") (pin "1") (pinfunction "1_1") (pintype "passive"))
    )
    (net (code "39") (name "Net-(IC8-VIN+)") (class "Default")
      (node (ref "C40") (pin "1") (pinfunction "1_1") (pintype "passive"))
      (node (ref "IC8") (pin "3") (pinfunction "VIN+_3") (pintype "input"))
      (node (ref "R46") (pin "1") (pinfunction "1_1") (pintype "passive"))
    )
    (net (code "40") (name "Net-(IC8-VIN-)") (class "Default")
      (node (ref "C40") (pin "2") (pinfunction "2_2") (pintype "passive"))
      (node (ref "IC8") (pin "4") (pinfunction "VIN-_4") (pintype "input"))
      (node (ref "R47") (pin "1") (pinfunction "1_1") (pintype "passive"))
    )
    (net (code "41") (name "Net-(IC9-ADCIN)") (class "Default")
      (node (ref "C48") (pin "2") (pinfunction "2_2") (pintype "passive"))
      (node (ref "IC9") (pin "14") (pinfunction "ADCIN_14") (pintype "input"))
      (node (ref "R56") (pin "2") (pinfunction "2_2") (pintype "passive"))
    )
    (net (code "42") (name "Net-(IC9-MUXOUT)") (class "Default")
      (node (ref "IC9") (pin "13") (pinfunction "MUXOUT_13") (pintype "output"))
      (node (ref "R56") (pin "1") (pinfunction "1_1") (pintype "passive"))
    )
    (net (code "43") (name "Net-(IC13-ADJ)") (class "Default")
      (node (ref "IC13") (pin "4") (pinfunction "ADJ_4") (pintype "input"))
      (node (ref "R86") (pin "1") (pinfunction "1_1") (pintype "passive"))
      (node (ref "R87") (pin "2") (pinfunction "2_2") (pintype "passive"))
    )
    (net (code "44") (name "Net-(IC13-~{SHDN})") (class "Default")
      (node (ref "IC13") (pin "3") (pinfunction "~{SHDN}_3") (pintype "input"))
      (node (ref "R54") (pin "2") (pinfunction "2_2") (pintype "passive"))
    )
    (net (code "45") (name "Net-(IC14-FLAG1)") (class "Default")
      (node (ref "IC14") (pin "6") (pinfunction "FLAG1_6") (pintype "output"))
      (node (ref "R32") (pin "2") (pinfunction "2_2") (pintype "passive"))
      (node (ref "R54") (pin "1") (pinfunction "1_1") (pintype "passive"))
    )
    (net (code "46") (name "Net-(IC14-FLAG2)") (class "Default")
      (node (ref "IC14") (pin "5") (pinfunction "FLAG2_5") (pintype "output"))
      (node (ref "IC3") (pin "1") (pinfunction "~{SHDN}_1") (pintype "input"))
      (node (ref "R51") (pin "2") (pinfunction "2_2") (pintype "passive"))
    )
    (net (code "47") (name "Net-(IC14-FLAG3)") (class "Default")
      (node (ref "IC14") (pin "4") (pinfunction "FLAG3_4") (pintype "output"))
      (node (ref "R52") (pin "2") (pinfunction "2_2") (pintype "passive"))
      (node (ref "T6") (pin "1") (pinfunction "G_1") (pintype "passive"))
    )
    (net (code "48") (name "Net-(IC15-A0)") (class "Default")
      (node (ref "IC15") (pin "6") (pinfunction "A0_6") (pintype "input"))
      (node (ref "R90") (pin "2") (pinfunction "2_2") (pintype "passive"))
    )
    (net (code "49") (name "Net-(IC15-VOUT)") (class "Default")
      (node (ref "IC15") (pin "1") (pinfunction "VOUT_1") (pintype "output"))
      (node (ref "R87") (pin "1") (pinfunction "1_1") (pintype "passive"))
      (node (ref "R89") (pin "1") (pinfunction "1_1") (pintype "passive"))
    )
    (net (code "50") (name "Net-(LD1-A)") (class "Default")
      (node (ref "LD1") (pin "2") (pinfunction "A_2") (pintype "passive"))
      (node (ref "R7") (pin "1") (pinfunction "1_1") (pintype "passive"))
    )
    (net (code "51") (name "Net-(LD2-A)") (class "Default")
      (node (ref "LD2") (pin "2") (pinfunction "A_2") (pintype "passive"))
      (node (ref "R11") (pin "2") (pinfunction "2_2") (pintype "passive"))
    )
    (net (code "52") (name "Net-(LD4-A)") (class "Default")
      (node (ref "LD4") (pin "2") (pinfunction "A_2") (pintype "passive"))
      (node (ref "R107") (pin "1") (pinfunction "1_1") (pintype "passive"))
    )
    (net (code "53") (name "Net-(LD12-C)") (class "Default")
      (node (ref "LD12") (pin "1") (pinfunction "C_1") (pintype "passive"))
      (node (ref "R104") (pin "2") (pinfunction "2_2") (pintype "passive"))
    )
    (net (code "54") (name "Net-(T1-B)") (class "Default")
      (node (ref "R12") (pin "1") (pinfunction "1_1") (pintype "passive"))
      (node (ref "R29") (pin "2") (pinfunction "2_2") (pintype "passive"))
      (node (ref "T1") (pin "1") (pinfunction "B_1") (pintype "passive"))
    )
    (net (code "55") (name "Net-(T1-C)") (class "Default")
      (node (ref "R37") (pin "2") (pinfunction "2_2") (pintype "passive"))
      (node (ref "R44") (pin "2") (pinfunction "2_2") (pintype "passive"))
      (node (ref "R7") (pin "2") (pinfunction "2_2") (pintype "passive"))
      (node (ref "R8") (pin "2") (pinfunction "2_2") (pintype "passive"))
      (node (ref "T1") (pin "3") (pinfunction "C_3") (pintype "passive"))
    )
    (net (code "56") (name "Net-(T1-E)") (class "Default")
      (node (ref "R12") (pin "2") (pinfunction "2_2") (pintype "passive"))
      (node (ref "T1") (pin "2") (pinfunction "E_2") (pintype "passive"))
      (node (ref "U1") (pin "8") (pinfunction "SENSE_RESISTOR_OUT_8") (pintype "passive"))
    )
    (net (code "57") (name "Net-(T2-D)") (class "Default")
      (node (ref "J1") (pin "14") (pinfunction "14_14") (pintype "bidirectional"))
      (node (ref "R84") (pin "1") (pinfunction "1_1") (pintype "passive"))
      (node (ref "T2") (pin "3") (pinfunction "D_3") (pintype "passive"))
    )
    (net (code "58") (name "Net-(T2-G)") (class "Default")
      (node (ref "R17") (pin "1") (pinfunction "1_1") (pintype "passive"))
      (node (ref "R40") (pin "1") (pinfunction "1_1") (pintype "passive"))
      (node (ref "T2") (pin "1") (pinfunction "G_1") (pintype "passive"))
      (node (ref "T3") (pin "1") (pinfunction "G_1") (pintype "passive"))
      (node (ref "T6") (pin "3") (pinfunction "D_3") (pintype "passive"))
    )
    (net (code "59") (name "Net-(T3-D)") (class "Default")
      (node (ref "C20") (pin "2") (pinfunction "2_2") (pintype "passive"))
      (node (ref "T3") (pin "3") (pinfunction "D_3") (pintype "passive"))
      (node (ref "U1") (pin "2") (pinfunction "COMPENSATION/SHUTDOWN_2") (pintype "passive"))
    )
    (net (code "60") (name "Net-(U1-DRIVER_SINK)") (class "Default")
      (node (ref "R29") (pin "1") (pinfunction "1_1") (pintype "passive"))
      (node (ref "U1") (pin "6") (pinfunction "DRIVER_SINK_6") (pintype "passive"))
    )
    (net (code "61") (name "Net-(U1-VOUT_SENSE)") (class "Default")
      (node (ref "R8") (pin "1") (pinfunction "1_1") (pintype "passive"))
      (node (ref "R9") (pin "2") (pinfunction "2_2") (pintype "passive"))
      (node (ref "U1") (pin "5") (pinfunction "VOUT_SENSE_5") (pintype "input"))
    )
    (net (code "62") (name "P3V3") (class "Default")
      (node (ref "C43") (pin "2") (pinfunction "2_2") (pintype "passive"))
      (node (ref "C45") (pin "2") (pinfunction "2_2") (pintype "passive"))
      (node (ref "C47") (pin "2") (pinfunction "2_2") (pintype "passive"))
      (node (ref "C50") (pin "1") (pinfunction "1_1") (pintype "passive"))
      (node (ref "C60") (pin "2") (pinfunction "2_2") (pintype "passive"))
      (node (ref "IC14") (pin "1") (pinfunction "VCC_1") (pintype "power_in"))
      (node (ref "IC15") (pin "3") (pinfunction "VDD_3") (pintype "power_in"))
      (node (ref "IC6") (pin "5") (pinfunction "V+_5") (pintype "power_in"))
      (node (ref "IC7") (pin "5") (pinfunction "V+_5") (pintype "power_in"))
      (node (ref "IC8") (pin "5") (pinfunction "V+_5") (pintype "power_in"))
      (node (ref "IC9") (pin "16") (pinfunction "DVDD_16") (pintype "power_in"))
      (node (ref "IC9") (pin "5") (pinfunction "A0_5") (pintype "input"))
      (node (ref "R107") (pin "2") (pinfunction "2_2") (pintype "passive"))
      (node (ref "R32") (pin "1") (pinfunction "1_1") (pintype "passive"))
      (node (ref "R51") (pin "1") (pinfunction "1_1") (pintype "passive"))
      (node (ref "R52") (pin "1") (pinfunction "1_1") (pintype "passive"))
      (node (ref "R57") (pin "2") (pinfunction "2_2") (pintype "passive"))
      (node (ref "R89") (pin "2") (pinfunction "2_2") (pintype "passive"))
    )
    (net (code "63") (name "P5V0") (class "Default")
      (node (ref "F1") (pin "1") (pinfunction "1_1") (pintype "passive"))
    )
    (net (code "64") (name "P6V5") (class "Default")
      (node (ref "C19") (pin "2") (pinfunction "2_2") (pintype "passive"))
      (node (ref "IC3") (pin "2") (pinfunction "IN_2") (pintype "input"))
    )
    (net (code "65") (name "P30V0") (class "Default")
      (node (ref "C32") (pin "2") (pinfunction "2_2") (pintype "passive"))
      (node (ref "R17") (pin "2") (pinfunction "2_2") (pintype "passive"))
      (node (ref "U1") (pin "1") (pinfunction "+VIN_1") (pintype "power_in"))
    )
    (net (code "66") (name "unconnected-(IC9-PWRCON-Pad7)") (class "Default")
      (node (ref "IC9") (pin "7") (pinfunction "PWRCON_7") (pintype "output"))
    )
    (net (code "67") (name "unconnected-(U1-CURRENT_LIMIT(-)-Pad7)") (class "Default")
      (node (ref "U1") (pin "7") (pinfunction "CURRENT_LIMIT(-)_7") (pintype "input"))
    )
  )
)
